# ROV_PCB_CHARGE.net
KiCad netlist of a schematic drawn in Altium Designer
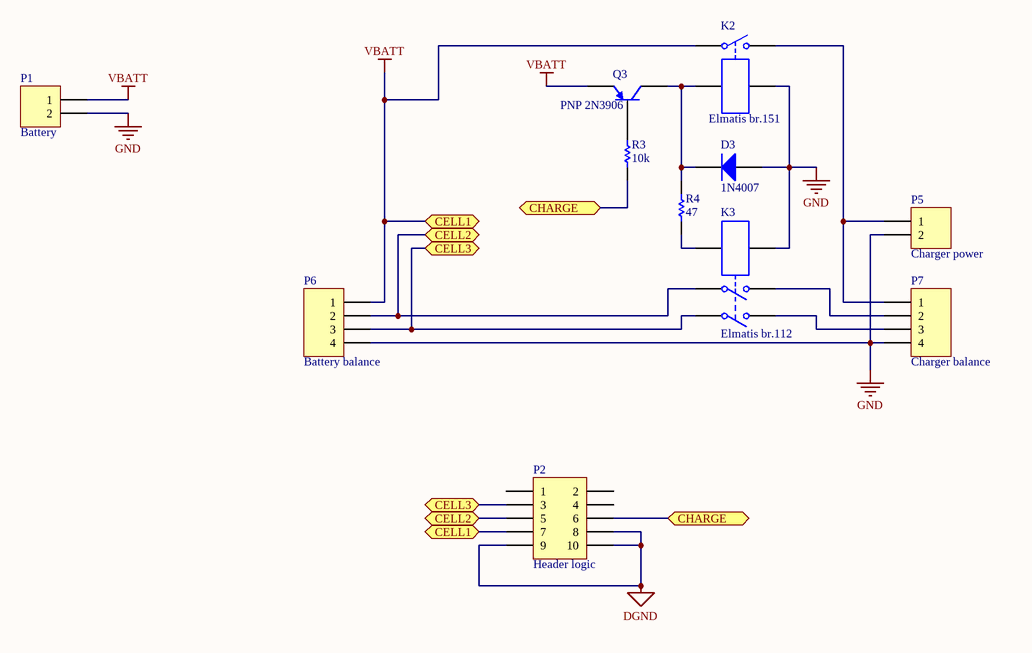
[diagram p0: ROV_PCB_CHARGE.SchDoc]

(export (version "E")
  (design (tool "Eeschema 10.0.6"))
  (components
    (comp (ref "D3")
      (value "1N4007")
      (footprint "DO-41")
      (description "1 Amp General Purpose Rectifier")
      (fields (field (name "PUBLISHER") "Altium Limited"))
      (libsource (lib "Miscellaneous Devices") (part "Diode 1N4007"))
    )
    (comp (ref "K2")
      (value "Elmatis br.151")
      (footprint "REL151")
      (description "Single-Pole Single-Throw Relay")
      (fields (field (name "PART NUMBER") "151") (field (name "PUBLISHER") "Altium Limited"))
      (libsource (lib "Miscellaneous Devices") (part "Relay-SPST"))
    )
    (comp (ref "K3")
      (value "Elmatis br.112")
      (footprint "REL112")
      (description "Dual-Pole Single-Throw Relay")
      (fields (field (name "PART NUMBER") "112") (field (name "PUBLISHER") "Altium Limited"))
      (libsource (lib "Miscellaneous Devices") (part "Relay-DPST"))
    )
    (comp (ref "P1")
      (value "Battery")
      (footprint "Klema")
      (description "Header, 2-Pin")
      (fields (field (name "PUBLISHER") "Altium Limited"))
      (libsource (lib "") (part "Header 2_1"))
    )
    (comp (ref "P2")
      (value "Header logic")
      (footprint "HDR2X5")
      (description "Header, 5-Pin, Dual row")
      (fields (field (name "PUBLISHER") "Altium Limited"))
      (libsource (lib "Miscellaneous Connectors") (part "Header 5X2"))
    )
    (comp (ref "P5")
      (value "Charger power")
      (footprint "Klema")
      (description "Header, 2-Pin")
      (fields (field (name "PUBLISHER") "Altium Limited"))
      (libsource (lib "Miscellaneous Connectors") (part "Header 2"))
    )
    (comp (ref "P6")
      (value "Battery balance")
      (footprint "HDR1X4")
      (description "Header, 4-Pin")
      (fields (field (name "PUBLISHER") "Altium Limited"))
      (libsource (lib "Miscellaneous Connectors") (part "Header 4"))
    )
    (comp (ref "P7")
      (value "Charger balance")
      (footprint "HDR1X4")
      (description "Header, 4-Pin")
      (fields (field (name "PUBLISHER") "Altium Limited"))
      (libsource (lib "") (part "Header 4_1"))
    )
    (comp (ref "Q3")
      (value "PNP 2N3906")
      (footprint "MHDR1X3")
      (description "PNP Bipolar Transistor")
      (fields (field (name "PUBLISHER") "Altium Limited"))
      (libsource (lib "Miscellaneous Devices") (part "PNP"))
    )
    (comp (ref "R3")
      (value "10k")
      (footprint "AXIAL-0.3")
      (description "Resistor")
      (fields (field (name "PUBLISHER") "Altium Limited"))
      (libsource (lib "Miscellaneous Devices") (part "Res1"))
    )
    (comp (ref "R4")
      (value "47")
      (footprint "AXIAL-0.3")
      (description "Resistor")
      (fields (field (name "PUBLISHER") "Altium Limited"))
      (libsource (lib "Miscellaneous Devices") (part "Res1"))
    )
  )
  (nets
    (net (code "1") (name "/CELL2") (class "Default")
      (node (ref "K3") (pin "3") (pinfunction "3_3") (pintype "passive"))
      (node (ref "P2") (pin "5") (pinfunction "5_5") (pintype "passive"))
      (node (ref "P6") (pin "2") (pinfunction "2_2") (pintype "passive"))
    )
    (net (code "2") (name "/CELL3") (class "Default")
      (node (ref "K3") (pin "1") (pinfunction "1_1") (pintype "passive"))
      (node (ref "P2") (pin "3") (pinfunction "3_3") (pintype "passive"))
      (node (ref "P6") (pin "3") (pinfunction "3_3") (pintype "passive"))
    )
    (net (code "3") (name "/CHARGE") (class "Default")
      (node (ref "P2") (pin "6") (pinfunction "6_6") (pintype "passive"))
      (node (ref "R3") (pin "1") (pinfunction "1_1") (pintype "passive"))
    )
    (net (code "4") (name "DGND") (class "Default")
      (node (ref "P2") (pin "10") (pinfunction "10_10") (pintype "passive"))
      (node (ref "P2") (pin "8") (pinfunction "8_8") (pintype "passive"))
      (node (ref "P2") (pin "9") (pinfunction "9_9") (pintype "passive"))
    )
    (net (code "5") (name "GND") (class "Default")
      (node (ref "D3") (pin "1") (pinfunction "A_1") (pintype "passive"))
      (node (ref "K2") (pin "4") (pinfunction "4_4") (pintype "passive"))
      (node (ref "K3") (pin "6") (pinfunction "6_6") (pintype "passive"))
      (node (ref "P1") (pin "2") (pinfunction "2_2") (pintype "passive"))
      (node (ref "P5") (pin "2") (pinfunction "2_2") (pintype "passive"))
      (node (ref "P6") (pin "4") (pinfunction "4_4") (pintype "passive"))
      (node (ref "P7") (pin "4") (pinfunction "4_4") (pintype "passive"))
    )
    (net (code "6") (name "Net-(D3-K)") (class "Default")
      (node (ref "D3") (pin "2") (pinfunction "K_2") (pintype "passive"))
      (node (ref "K2") (pin "3") (pinfunction "3_3") (pintype "passive"))
      (node (ref "Q3") (pin "3") (pinfunction "C_3") (pintype "passive"))
      (node (ref "R4") (pin "2") (pinfunction "2_2") (pintype "passive"))
    )
    (net (code "7") (name "Net-(K2-Pad2)") (class "Default")
      (node (ref "K2") (pin "2") (pinfunction "2_2") (pintype "passive"))
      (node (ref "P5") (pin "1") (pinfunction "1_1") (pintype "passive"))
      (node (ref "P7") (pin "1") (pinfunction "1_1") (pintype "passive"))
    )
    (net (code "8") (name "Net-(K3-Pad2)") (class "Default")
      (node (ref "K3") (pin "2") (pinfunction "2_2") (pintype "passive"))
      (node (ref "P7") (pin "3") (pinfunction "3_3") (pintype "passive"))
    )
    (net (code "9") (name "Net-(K3-Pad4)") (class "Default")
      (node (ref "K3") (pin "4") (pinfunction "4_4") (pintype "passive"))
      (node (ref "P7") (pin "2") (pinfunction "2_2") (pintype "passive"))
    )
    (net (code "10") (name "Net-(K3-Pad5)") (class "Default")
      (node (ref "K3") (pin "5") (pinfunction "5_5") (pintype "passive"))
      (node (ref "R4") (pin "1") (pinfunction "1_1") (pintype "passive"))
    )
    (net (code "11") (name "Net-(Q3-B)") (class "Default")
      (node (ref "Q3") (pin "2") (pinfunction "B_2") (pintype "passive"))
      (node (ref "R3") (pin "2") (pinfunction "2_2") (pintype "passive"))
    )
    (net (code "12") (name "VBATT") (class "Default")
      (node (ref "K2") (pin "1") (pinfunction "1_1") (pintype "passive"))
      (node (ref "P1") (pin "1") (pinfunction "1_1") (pintype "passive"))
      (node (ref "P2") (pin "7") (pinfunction "7_7") (pintype "passive"))
      (node (ref "P6") (pin "1") (pinfunction "1_1") (pintype "passive"))
      (node (ref "Q3") (pin "1") (pinfunction "E_1") (pintype "passive"))
    )
    (net (code "13") (name "unconnected-(P2-Pad1)") (class "Default")
      (node (ref "P2") (pin "1") (pinfunction "1_1") (pintype "passive"))
    )
    (net (code "14") (name "unconnected-(P2-Pad2)") (class "Default")
      (node (ref "P2") (pin "2") (pinfunction "2_2") (pintype "passive"))
    )
    (net (code "15") (name "unconnected-(P2-Pad4)") (class "Default")
      (node (ref "P2") (pin "4") (pinfunction "4_4") (pintype "passive"))
    )
  )
)
